# Game_Consol_Top.net
KiCad netlist of a schematic drawn in Altium Designer
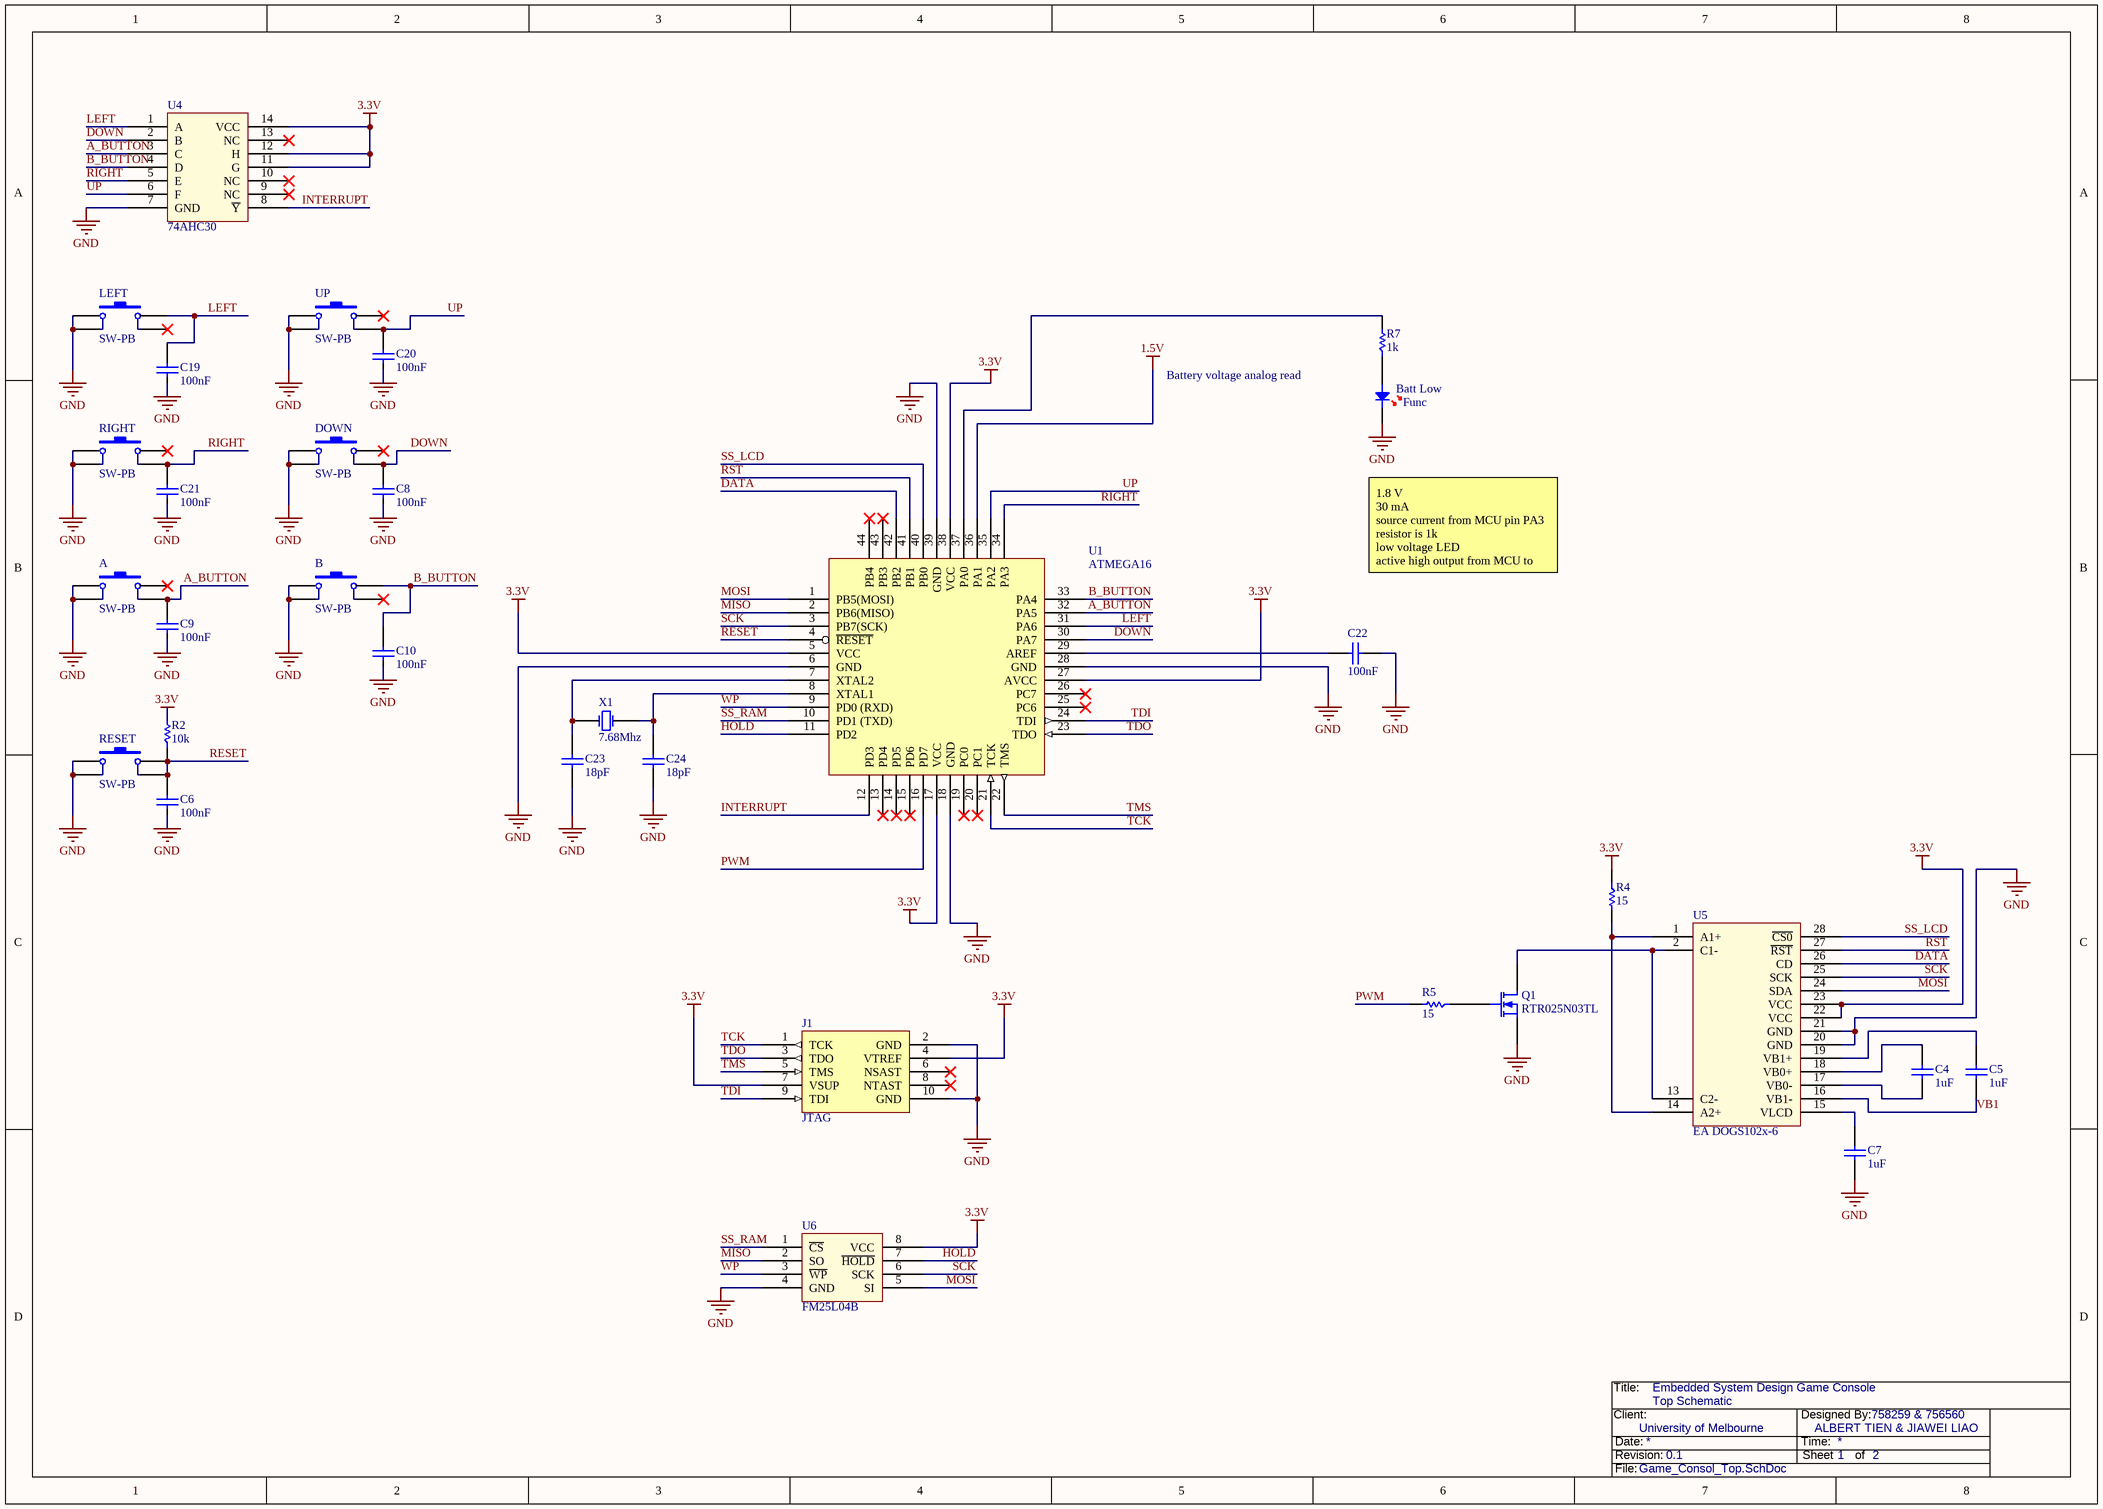
[diagram p0: Game_Consol_Top.SchDoc]

(export (version "E")
  (design (tool "Eeschema 10.0.6"))
  (components
    (comp (ref "A")
      (value "SW-PB")
      (footprint "SPNO_SMD")
      (description "Push Button Switch")
      (fields
        (field (name "MANUFACTURER") "TE Connectivity")
        (field (name "MANUFACTURER PART NUMBER") "FSM4JSMA")
        (field (name "PUBLISHER") "Altium Limited")
      )
      (libsource (lib "EmbSD Lib 0v1") (part "SW-PB"))
    )
    (comp (ref "B")
      (value "SW-PB")
      (footprint "SPNO_SMD")
      (description "Push Button Switch")
      (fields
        (field (name "MANUFACTURER") "TE Connectivity")
        (field (name "MANUFACTURER PART NUMBER") "FSM4JSMA")
        (field (name "PUBLISHER") "Altium Limited")
      )
      (libsource (lib "EmbSD Lib 0v1") (part "SW-PB"))
    )
    (comp (ref "Batt Low")
      (value "Func")
      (footprint "0805D")
      (description "Light Emitting Diode")
      (fields (field (name "MANUFACTURER") "Generic Components") (field (name "PUBLISHER") "Altium Limited"))
      (libsource (lib "EmbSD Lib 0v1") (part "LED RED"))
    )
    (comp (ref "C4")
      (value "1uF")
      (footprint "0805")
      (description "Capacitor 100nF")
      (libsource (lib "EmbSD Lib 0v1") (part "C 0805"))
    )
    (comp (ref "C5")
      (value "1uF")
      (footprint "0805")
      (description "Capacitor 100nF")
      (libsource (lib "EmbSD Lib 0v1") (part "C 0805"))
    )
    (comp (ref "C6")
      (value "100nF")
      (footprint "0805")
      (description "Capacitor 100nF")
      (libsource (lib "EmbSD Lib 0v1") (part "C 0805"))
    )
    (comp (ref "C7")
      (value "1uF")
      (footprint "0805")
      (description "Capacitor 100nF")
      (libsource (lib "EmbSD Lib 0v1") (part "C 0805"))
    )
    (comp (ref "C8")
      (value "100nF")
      (footprint "0805")
      (description "Capacitor 100nF")
      (libsource (lib "EmbSD Lib 0v1") (part "C 0805"))
    )
    (comp (ref "C9")
      (value "100nF")
      (footprint "0805")
      (description "Capacitor 100nF")
      (libsource (lib "EmbSD Lib 0v1") (part "C 0805"))
    )
    (comp (ref "C10")
      (value "100nF")
      (footprint "0805")
      (description "Capacitor 100nF")
      (libsource (lib "EmbSD Lib 0v1") (part "C 0805"))
    )
    (comp (ref "C19")
      (value "100nF")
      (footprint "0805")
      (description "Capacitor 100nF")
      (libsource (lib "EmbSD Lib 0v1") (part "C 0805"))
    )
    (comp (ref "C20")
      (value "100nF")
      (footprint "0805")
      (description "Capacitor 100nF")
      (libsource (lib "EmbSD Lib 0v1") (part "C 0805"))
    )
    (comp (ref "C21")
      (value "100nF")
      (footprint "0805")
      (description "Capacitor 100nF")
      (libsource (lib "EmbSD Lib 0v1") (part "C 0805"))
    )
    (comp (ref "C22")
      (value "100nF")
      (footprint "0805")
      (description "Capacitor 100nF")
      (libsource (lib "EmbSD Lib 0v1") (part "C 0805"))
    )
    (comp (ref "C23")
      (value "~")
      (footprint "0805")
      (description "Capacitor 100nF")
      (fields (field (name "ALTIUM_UNNAMED_1") "18pF"))
      (libsource (lib "EmbSD Lib 0v1") (part "C 0805"))
    )
    (comp (ref "C24")
      (value "18pF")
      (footprint "0805")
      (description "Capacitor 100nF")
      (libsource (lib "EmbSD Lib 0v1") (part "C 0805"))
    )
    (comp (ref "DOWN")
      (value "SW-PB")
      (footprint "SPNO_SMD")
      (description "Push Button Switch")
      (fields
        (field (name "MANUFACTURER") "TE Connectivity")
        (field (name "MANUFACTURER PART NUMBER") "FSM4JSMA")
        (field (name "PUBLISHER") "Altium Limited")
      )
      (libsource (lib "EmbSD Lib 0v1") (part "SW-PB"))
    )
    (comp (ref "J1")
      (value "JTAG")
      (footprint "BOXEDVERT10")
      (description "JTAG ATMEL connector")
      (libsource (lib "EmbSD Lib 0v1") (part "JTAG_CON"))
    )
    (comp (ref "LEFT")
      (value "SW-PB")
      (footprint "SPNO_SMD")
      (description "Push Button Switch")
      (fields
        (field (name "MANUFACTURER") "TE Connectivity")
        (field (name "MANUFACTURER PART NUMBER") "FSM4JSMA")
        (field (name "PUBLISHER") "Altium Limited")
      )
      (libsource (lib "EmbSD Lib 0v1") (part "SW-PB"))
    )
    (comp (ref "Q1")
      (value "RTR025N03TL")
      (footprint "SOT23")
      (description "N-Channel MOSFET")
      (fields (field (name "PUBLISHER") "Altium Limited"))
      (libsource (lib "EmbSD Lib 0v1") (part "MOSFET-N"))
    )
    (comp (ref "R2")
      (value "10k")
      (footprint "0805")
      (description "Resistor")
      (libsource (lib "EmbSD Lib 0v1") (part "R"))
    )
    (comp (ref "R4")
      (value "15")
      (footprint "0805")
      (description "Resistor")
      (libsource (lib "EmbSD Lib 0v1") (part "R"))
    )
    (comp (ref "R5")
      (value "15")
      (footprint "0805")
      (description "Resistor")
      (libsource (lib "EmbSD Lib 0v1") (part "R"))
    )
    (comp (ref "R7")
      (value "1k")
      (footprint "0805")
      (description "Resistor")
      (libsource (lib "EmbSD Lib 0v1") (part "R"))
    )
    (comp (ref "RESET")
      (value "SW-PB")
      (footprint "SPNO_SMD")
      (description "Push Button Switch")
      (fields
        (field (name "MANUFACTURER") "TE Connectivity")
        (field (name "MANUFACTURER PART NUMBER") "FSM4JSMA")
        (field (name "PUBLISHER") "Altium Limited")
      )
      (libsource (lib "EmbSD Lib 0v1") (part "SW-PB"))
    )
    (comp (ref "RIGHT")
      (value "SW-PB")
      (footprint "SPNO_SMD")
      (description "Push Button Switch")
      (fields
        (field (name "MANUFACTURER") "TE Connectivity")
        (field (name "MANUFACTURER PART NUMBER") "FSM4JSMA")
        (field (name "PUBLISHER") "Altium Limited")
      )
      (libsource (lib "EmbSD Lib 0v1") (part "SW-PB"))
    )
    (comp (ref "U1")
      (value "ATMEGA16")
      (footprint "QFP-48")
      (description "ATMEGA16 Microcontroller")
      (libsource (lib "EmbSD Lib 0v1") (part "ATMEGA16"))
    )
    (comp (ref "U4")
      (value "74AHC30")
      (footprint "SOIC-14")
      (description "1 x 8 Input NAND gate")
      (libsource (lib "EmbSD Lib 0v1") (part "74AHC30"))
    )
    (comp (ref "U5")
      (value "EA DOGS102x-6")
      (footprint "EA DOGS102x")
      (description "LCD 102x64-pixel with backlight")
      (libsource (lib "EmbSD Lib 0v1") (part "EA DOGS102x-6"))
    )
    (comp (ref "U6")
      (value "FM25L04B")
      (footprint "SOIC-8")
      (description "FRAM 4Kb Memory")
      (libsource (lib "EmbSD Lib 0v1") (part "FM25L04B"))
    )
    (comp (ref "UP")
      (value "SW-PB")
      (footprint "SPNO_SMD")
      (description "Push Button Switch")
      (fields
        (field (name "MANUFACTURER") "TE Connectivity")
        (field (name "MANUFACTURER PART NUMBER") "FSM4JSMA")
        (field (name "PUBLISHER") "Altium Limited")
      )
      (libsource (lib "EmbSD Lib 0v1") (part "SW-PB"))
    )
    (comp (ref "X1")
      (value "7.68Mhz")
      (footprint "XTAL_FLAT_SMD")
      (description "Crystal Oscillator")
      (libsource (lib "EmbSD Lib 0v1") (part "XTAL"))
    )
  )
  (nets
    (net (code "1") (name "/A_BUTTON") (class "Default")
      (node (ref "A") (pin "4") (pinfunction "4_4") (pintype "passive"))
      (node (ref "C9") (pin "1") (pinfunction "1_1") (pintype "passive"))
      (node (ref "U1") (pin "32") (pinfunction "PA5_32") (pintype "passive"))
      (node (ref "U4") (pin "3") (pinfunction "C_3") (pintype "passive"))
    )
    (net (code "2") (name "/B_BUTTON") (class "Default")
      (node (ref "B") (pin "3") (pinfunction "3_3") (pintype "passive"))
      (node (ref "C10") (pin "1") (pinfunction "1_1") (pintype "passive"))
      (node (ref "U1") (pin "33") (pinfunction "PA4_33") (pintype "passive"))
      (node (ref "U4") (pin "4") (pinfunction "D_4") (pintype "passive"))
    )
    (net (code "3") (name "/DATA") (class "Default")
      (node (ref "U1") (pin "42") (pinfunction "PB2_42") (pintype "passive"))
      (node (ref "U5") (pin "26") (pinfunction "CD_26") (pintype "passive"))
    )
    (net (code "4") (name "/DOWN") (class "Default")
      (node (ref "C8") (pin "1") (pinfunction "1_1") (pintype "passive"))
      (node (ref "DOWN") (pin "4") (pinfunction "4_4") (pintype "passive"))
      (node (ref "U1") (pin "30") (pinfunction "PA7_30") (pintype "passive"))
      (node (ref "U4") (pin "2") (pinfunction "B_2") (pintype "passive"))
    )
    (net (code "5") (name "/HOLD") (class "Default")
      (node (ref "U1") (pin "11") (pinfunction "PD2_11") (pintype "passive"))
      (node (ref "U6") (pin "7") (pinfunction "~{HOLD}_7") (pintype "passive"))
    )
    (net (code "6") (name "/INTERRUPT") (class "Default")
      (node (ref "U1") (pin "12") (pinfunction "PD3_12") (pintype "passive"))
      (node (ref "U4") (pin "8") (pinfunction "~{Y}_8") (pintype "passive"))
    )
    (net (code "7") (name "/LEFT") (class "Default")
      (node (ref "C19") (pin "1") (pinfunction "1_1") (pintype "passive"))
      (node (ref "LEFT") (pin "3") (pinfunction "3_3") (pintype "passive"))
      (node (ref "U1") (pin "31") (pinfunction "PA6_31") (pintype "passive"))
      (node (ref "U4") (pin "1") (pinfunction "A_1") (pintype "passive"))
    )
    (net (code "8") (name "/MISO") (class "Default")
      (node (ref "U1") (pin "2") (pinfunction "PB6(MISO)_2") (pintype "passive"))
      (node (ref "U6") (pin "2") (pinfunction "SO_2") (pintype "passive"))
    )
    (net (code "9") (name "/MOSI") (class "Default")
      (node (ref "U1") (pin "1") (pinfunction "PB5(MOSI)_1") (pintype "passive"))
      (node (ref "U5") (pin "24") (pinfunction "SDA_24") (pintype "passive"))
      (node (ref "U6") (pin "5") (pinfunction "SI_5") (pintype "passive"))
    )
    (net (code "10") (name "/PWM") (class "Default")
      (node (ref "R5") (pin "2") (pintype "passive"))
      (node (ref "U1") (pin "16") (pinfunction "PD7_16") (pintype "passive"))
    )
    (net (code "11") (name "/RESET") (class "Default")
      (node (ref "C6") (pin "1") (pinfunction "1_1") (pintype "passive"))
      (node (ref "R2") (pin "1") (pintype "passive"))
      (node (ref "RESET") (pin "3") (pinfunction "3_3") (pintype "passive"))
      (node (ref "RESET") (pin "4") (pinfunction "4_4") (pintype "passive"))
      (node (ref "U1") (pin "4") (pinfunction "~{RESET}_4") (pintype "passive"))
    )
    (net (code "12") (name "/RIGHT") (class "Default")
      (node (ref "C21") (pin "1") (pinfunction "1_1") (pintype "passive"))
      (node (ref "RIGHT") (pin "4") (pinfunction "4_4") (pintype "passive"))
      (node (ref "U1") (pin "34") (pinfunction "PA3_34") (pintype "passive"))
      (node (ref "U4") (pin "5") (pinfunction "E_5") (pintype "passive"))
    )
    (net (code "13") (name "/RST") (class "Default")
      (node (ref "U1") (pin "41") (pinfunction "PB1_41") (pintype "passive"))
      (node (ref "U5") (pin "27") (pinfunction "~{RST}_27") (pintype "passive"))
    )
    (net (code "14") (name "/SCK") (class "Default")
      (node (ref "U1") (pin "3") (pinfunction "PB7(SCK)_3") (pintype "passive"))
      (node (ref "U5") (pin "25") (pinfunction "SCK_25") (pintype "passive"))
      (node (ref "U6") (pin "6") (pinfunction "SCK_6") (pintype "passive"))
    )
    (net (code "15") (name "/SS_LCD") (class "Default")
      (node (ref "U1") (pin "40") (pinfunction "PB0_40") (pintype "passive"))
      (node (ref "U5") (pin "28") (pinfunction "~{CS0}_28") (pintype "passive"))
    )
    (net (code "16") (name "/SS_RAM") (class "Default")
      (node (ref "U1") (pin "10") (pinfunction "PD1_(TXD)_10") (pintype "passive"))
      (node (ref "U6") (pin "1") (pinfunction "~{CS}_1") (pintype "passive"))
    )
    (net (code "17") (name "/TCK") (class "Default")
      (node (ref "J1") (pin "1") (pinfunction "TCK_1") (pintype "output"))
      (node (ref "U1") (pin "21") (pinfunction "TCK_21") (pintype "input"))
    )
    (net (code "18") (name "/TDI") (class "Default")
      (node (ref "J1") (pin "9") (pinfunction "TDI_9") (pintype "input"))
      (node (ref "U1") (pin "24") (pinfunction "TDI_24") (pintype "output"))
    )
    (net (code "19") (name "/TDO") (class "Default")
      (node (ref "J1") (pin "3") (pinfunction "TDO_3") (pintype "output"))
      (node (ref "U1") (pin "23") (pinfunction "TDO_23") (pintype "input"))
    )
    (net (code "20") (name "/TMS") (class "Default")
      (node (ref "J1") (pin "5") (pinfunction "TMS_5") (pintype "input"))
      (node (ref "U1") (pin "22") (pinfunction "TMS_22") (pintype "output"))
    )
    (net (code "21") (name "/UP") (class "Default")
      (node (ref "C20") (pin "1") (pinfunction "1_1") (pintype "passive"))
      (node (ref "U1") (pin "35") (pinfunction "PA2_35") (pintype "passive"))
      (node (ref "U4") (pin "6") (pinfunction "F_6") (pintype "passive"))
      (node (ref "UP") (pin "4") (pinfunction "4_4") (pintype "passive"))
    )
    (net (code "22") (name "/VB1") (class "Default")
      (node (ref "C5") (pin "2") (pinfunction "2_2") (pintype "passive"))
      (node (ref "U5") (pin "16") (pinfunction "VB1-_16") (pintype "passive"))
    )
    (net (code "23") (name "/WP") (class "Default")
      (node (ref "U1") (pin "9") (pinfunction "PD0_(RXD)_9") (pintype "passive"))
      (node (ref "U6") (pin "3") (pinfunction "~{WP}_3") (pintype "passive"))
    )
    (net (code "24") (name "1.5V") (class "Default")
      (node (ref "U1") (pin "36") (pinfunction "PA1_36") (pintype "passive"))
    )
    (net (code "25") (name "3.3V") (class "Default")
      (node (ref "J1") (pin "4") (pinfunction "VTREF_4") (pintype "power_in"))
      (node (ref "J1") (pin "7") (pinfunction "VSUP_7") (pintype "passive"))
      (node (ref "R2") (pin "2") (pintype "passive"))
      (node (ref "R4") (pin "1") (pintype "passive"))
      (node (ref "U1") (pin "17") (pinfunction "VCC_17") (pintype "passive"))
      (node (ref "U1") (pin "27") (pinfunction "AVCC_27") (pintype "passive"))
      (node (ref "U1") (pin "38") (pinfunction "VCC_38") (pintype "passive"))
      (node (ref "U1") (pin "5") (pinfunction "VCC_5") (pintype "passive"))
      (node (ref "U4") (pin "11") (pinfunction "G_11") (pintype "passive"))
      (node (ref "U4") (pin "12") (pinfunction "H_12") (pintype "passive"))
      (node (ref "U4") (pin "14") (pinfunction "VCC_14") (pintype "passive"))
      (node (ref "U5") (pin "22") (pinfunction "VCC_22") (pintype "passive"))
      (node (ref "U5") (pin "23") (pinfunction "VCC_23") (pintype "passive"))
      (node (ref "U6") (pin "8") (pinfunction "VCC_8") (pintype "passive"))
    )
    (net (code "26") (name "GND") (class "Default")
      (node (ref "A") (pin "1") (pinfunction "1_1") (pintype "passive"))
      (node (ref "A") (pin "2") (pinfunction "2_2") (pintype "passive"))
      (node (ref "B") (pin "1") (pinfunction "1_1") (pintype "passive"))
      (node (ref "B") (pin "2") (pinfunction "2_2") (pintype "passive"))
      (node (ref "Batt Low") (pin "K") (pinfunction "K_K") (pintype "passive"))
      (node (ref "C10") (pin "2") (pinfunction "2_2") (pintype "passive"))
      (node (ref "C19") (pin "2") (pinfunction "2_2") (pintype "passive"))
      (node (ref "C20") (pin "2") (pinfunction "2_2") (pintype "passive"))
      (node (ref "C21") (pin "2") (pinfunction "2_2") (pintype "passive"))
      (node (ref "C22") (pin "1") (pinfunction "1_1") (pintype "passive"))
      (node (ref "C23") (pin "2") (pinfunction "2_2") (pintype "passive"))
      (node (ref "C24") (pin "2") (pinfunction "2_2") (pintype "passive"))
      (node (ref "C6") (pin "2") (pinfunction "2_2") (pintype "passive"))
      (node (ref "C7") (pin "2") (pinfunction "2_2") (pintype "passive"))
      (node (ref "C8") (pin "2") (pinfunction "2_2") (pintype "passive"))
      (node (ref "C9") (pin "2") (pinfunction "2_2") (pintype "passive"))
      (node (ref "DOWN") (pin "1") (pinfunction "1_1") (pintype "passive"))
      (node (ref "DOWN") (pin "2") (pinfunction "2_2") (pintype "passive"))
      (node (ref "J1") (pin "10") (pinfunction "GND_10") (pintype "passive"))
      (node (ref "J1") (pin "2") (pinfunction "GND_2") (pintype "passive"))
      (node (ref "LEFT") (pin "1") (pinfunction "1_1") (pintype "passive"))
      (node (ref "LEFT") (pin "2") (pinfunction "2_2") (pintype "passive"))
      (node (ref "Q1") (pin "2") (pinfunction "2_2") (pintype "passive"))
      (node (ref "RESET") (pin "1") (pinfunction "1_1") (pintype "passive"))
      (node (ref "RESET") (pin "2") (pinfunction "2_2") (pintype "passive"))
      (node (ref "RIGHT") (pin "1") (pinfunction "1_1") (pintype "passive"))
      (node (ref "RIGHT") (pin "2") (pinfunction "2_2") (pintype "passive"))
      (node (ref "U1") (pin "18") (pinfunction "GND_18") (pintype "passive"))
      (node (ref "U1") (pin "28") (pinfunction "GND_28") (pintype "passive"))
      (node (ref "U1") (pin "39") (pinfunction "GND_39") (pintype "passive"))
      (node (ref "U1") (pin "6") (pinfunction "GND_6") (pintype "passive"))
      (node (ref "U4") (pin "7") (pinfunction "GND_7") (pintype "passive"))
      (node (ref "U5") (pin "20") (pinfunction "GND_20") (pintype "passive"))
      (node (ref "U5") (pin "21") (pinfunction "GND_21") (pintype "passive"))
      (node (ref "U6") (pin "4") (pinfunction "GND_4") (pintype "passive"))
      (node (ref "UP") (pin "1") (pinfunction "1_1") (pintype "passive"))
      (node (ref "UP") (pin "2") (pinfunction "2_2") (pintype "passive"))
    )
    (net (code "27") (name "Net-(Batt Low-PadA)") (class "Default")
      (node (ref "Batt Low") (pin "A") (pinfunction "A_A") (pintype "passive"))
      (node (ref "R7") (pin "1") (pintype "passive"))
    )
    (net (code "28") (name "Net-(Q1-Pad1)") (class "Default")
      (node (ref "Q1") (pin "1") (pinfunction "1_1") (pintype "passive"))
      (node (ref "R5") (pin "1") (pintype "passive"))
    )
    (net (code "29") (name "Net-(U1-AREF)") (class "Default")
      (node (ref "C22") (pin "2") (pinfunction "2_2") (pintype "passive"))
      (node (ref "U1") (pin "29") (pinfunction "AREF_29") (pintype "passive"))
    )
    (net (code "30") (name "Net-(U1-PA0)") (class "Default")
      (node (ref "R7") (pin "2") (pintype "passive"))
      (node (ref "U1") (pin "37") (pinfunction "PA0_37") (pintype "passive"))
    )
    (net (code "31") (name "Net-(U1-XTAL1)") (class "Default")
      (node (ref "C24") (pin "1") (pinfunction "1_1") (pintype "passive"))
      (node (ref "U1") (pin "8") (pinfunction "XTAL1_8") (pintype "passive"))
      (node (ref "X1") (pin "1") (pinfunction "OSC1_1") (pintype "passive"))
    )
    (net (code "32") (name "Net-(U1-XTAL2)") (class "Default")
      (node (ref "C23") (pin "1") (pinfunction "1_1") (pintype "passive"))
      (node (ref "U1") (pin "7") (pinfunction "XTAL2_7") (pintype "passive"))
      (node (ref "X1") (pin "2") (pinfunction "OSC2_2") (pintype "passive"))
    )
    (net (code "33") (name "Net-(U5-A1+)") (class "Default")
      (node (ref "R4") (pin "2") (pintype "passive"))
      (node (ref "U5") (pin "1") (pinfunction "A1+_1") (pintype "passive"))
      (node (ref "U5") (pin "14") (pinfunction "A2+_14") (pintype "passive"))
    )
    (net (code "34") (name "Net-(U5-C1-)") (class "Default")
      (node (ref "Q1") (pin "3") (pinfunction "3_3") (pintype "passive"))
      (node (ref "U5") (pin "13") (pinfunction "C2-_13") (pintype "passive"))
      (node (ref "U5") (pin "2") (pinfunction "C1-_2") (pintype "passive"))
    )
    (net (code "35") (name "Net-(U5-VB0+)") (class "Default")
      (node (ref "C4") (pin "1") (pinfunction "1_1") (pintype "passive"))
      (node (ref "U5") (pin "18") (pinfunction "VB0+_18") (pintype "passive"))
    )
    (net (code "36") (name "Net-(U5-VB0-)") (class "Default")
      (node (ref "C4") (pin "2") (pinfunction "2_2") (pintype "passive"))
      (node (ref "U5") (pin "17") (pinfunction "VB0-_17") (pintype "passive"))
    )
    (net (code "37") (name "Net-(U5-VB1+)") (class "Default")
      (node (ref "C5") (pin "1") (pinfunction "1_1") (pintype "passive"))
      (node (ref "U5") (pin "19") (pinfunction "VB1+_19") (pintype "passive"))
    )
    (net (code "38") (name "Net-(U5-VLCD)") (class "Default")
      (node (ref "C7") (pin "1") (pinfunction "1_1") (pintype "passive"))
      (node (ref "U5") (pin "15") (pinfunction "VLCD_15") (pintype "passive"))
    )
    (net (code "39") (name "unconnected-(A-Pad3)") (class "Default")
      (node (ref "A") (pin "3") (pinfunction "3_3") (pintype "passive+no_connect"))
    )
    (net (code "40") (name "unconnected-(B-Pad4)") (class "Default")
      (node (ref "B") (pin "4") (pinfunction "4_4") (pintype "passive+no_connect"))
    )
    (net (code "41") (name "unconnected-(DOWN-Pad3)") (class "Default")
      (node (ref "DOWN") (pin "3") (pinfunction "3_3") (pintype "passive+no_connect"))
    )
    (net (code "42") (name "unconnected-(J1-NSAST-Pad6)") (class "Default")
      (node (ref "J1") (pin "6") (pinfunction "NSAST_6") (pintype "passive+no_connect"))
    )
    (net (code "43") (name "unconnected-(J1-NTAST-Pad8)") (class "Default")
      (node (ref "J1") (pin "8") (pinfunction "NTAST_8") (pintype "passive+no_connect"))
    )
    (net (code "44") (name "unconnected-(LEFT-Pad4)") (class "Default")
      (node (ref "LEFT") (pin "4") (pinfunction "4_4") (pintype "passive+no_connect"))
    )
    (net (code "45") (name "unconnected-(RIGHT-Pad3)") (class "Default")
      (node (ref "RIGHT") (pin "3") (pinfunction "3_3") (pintype "passive+no_connect"))
    )
    (net (code "46") (name "unconnected-(U1-PB3-Pad43)") (class "Default")
      (node (ref "U1") (pin "43") (pinfunction "PB3_43") (pintype "passive+no_connect"))
    )
    (net (code "47") (name "unconnected-(U1-PB4-Pad44)") (class "Default")
      (node (ref "U1") (pin "44") (pinfunction "PB4_44") (pintype "passive+no_connect"))
    )
    (net (code "48") (name "unconnected-(U1-PC0-Pad19)") (class "Default")
      (node (ref "U1") (pin "19") (pinfunction "PC0_19") (pintype "passive+no_connect"))
    )
    (net (code "49") (name "unconnected-(U1-PC1-Pad20)") (class "Default")
      (node (ref "U1") (pin "20") (pinfunction "PC1_20") (pintype "passive+no_connect"))
    )
    (net (code "50") (name "unconnected-(U1-PC6-Pad25)") (class "Default")
      (node (ref "U1") (pin "25") (pinfunction "PC6_25") (pintype "passive+no_connect"))
    )
    (net (code "51") (name "unconnected-(U1-PC7-Pad26)") (class "Default")
      (node (ref "U1") (pin "26") (pinfunction "PC7_26") (pintype "passive+no_connect"))
    )
    (net (code "52") (name "unconnected-(U1-PD4-Pad13)") (class "Default")
      (node (ref "U1") (pin "13") (pinfunction "PD4_13") (pintype "passive+no_connect"))
    )
    (net (code "53") (name "unconnected-(U1-PD5-Pad14)") (class "Default")
      (node (ref "U1") (pin "14") (pinfunction "PD5_14") (pintype "passive+no_connect"))
    )
    (net (code "54") (name "unconnected-(U1-PD6-Pad15)") (class "Default")
      (node (ref "U1") (pin "15") (pinfunction "PD6_15") (pintype "passive+no_connect"))
    )
    (net (code "55") (name "unconnected-(U4-NC-Pad9)") (class "Default")
      (node (ref "U4") (pin "9") (pinfunction "NC_9") (pintype "passive+no_connect"))
    )
    (net (code "56") (name "unconnected-(U4-NC-Pad10)") (class "Default")
      (node (ref "U4") (pin "10") (pinfunction "NC_10") (pintype "passive+no_connect"))
    )
    (net (code "57") (name "unconnected-(U4-NC-Pad13)") (class "Default")
      (node (ref "U4") (pin "13") (pinfunction "NC_13") (pintype "passive+no_connect"))
    )
    (net (code "58") (name "unconnected-(U5-Pad3)") (class "Default")
      (node (ref "U5") (pin "3") (pinfunction "3_3") (pintype "passive"))
    )
    (net (code "59") (name "unconnected-(U5-Pad4)") (class "Default")
      (node (ref "U5") (pin "4") (pinfunction "4_4") (pintype "passive"))
    )
    (net (code "60") (name "unconnected-(U5-Pad5)") (class "Default")
      (node (ref "U5") (pin "5") (pinfunction "5_5") (pintype "passive"))
    )
    (net (code "61") (name "unconnected-(U5-Pad6)") (class "Default")
      (node (ref "U5") (pin "6") (pinfunction "6_6") (pintype "passive"))
    )
    (net (code "62") (name "unconnected-(U5-Pad7)") (class "Default")
      (node (ref "U5") (pin "7") (pinfunction "7_7") (pintype "passive"))
    )
    (net (code "63") (name "unconnected-(U5-Pad8)") (class "Default")
      (node (ref "U5") (pin "8") (pinfunction "8_8") (pintype "passive"))
    )
    (net (code "64") (name "unconnected-(U5-Pad9)") (class "Default")
      (node (ref "U5") (pin "9") (pinfunction "9_9") (pintype "passive"))
    )
    (net (code "65") (name "unconnected-(U5-Pad10)") (class "Default")
      (node (ref "U5") (pin "10") (pinfunction "10_10") (pintype "passive"))
    )
    (net (code "66") (name "unconnected-(U5-Pad11)") (class "Default")
      (node (ref "U5") (pin "11") (pinfunction "11_11") (pintype "passive"))
    )
    (net (code "67") (name "unconnected-(U5-Pad12)") (class "Default")
      (node (ref "U5") (pin "12") (pinfunction "12_12") (pintype "passive"))
    )
    (net (code "68") (name "unconnected-(UP-Pad3)") (class "Default")
      (node (ref "UP") (pin "3") (pinfunction "3_3") (pintype "passive+no_connect"))
    )
  )
)
